# imu.net
KiCad netlist of a schematic drawn in EAGLE
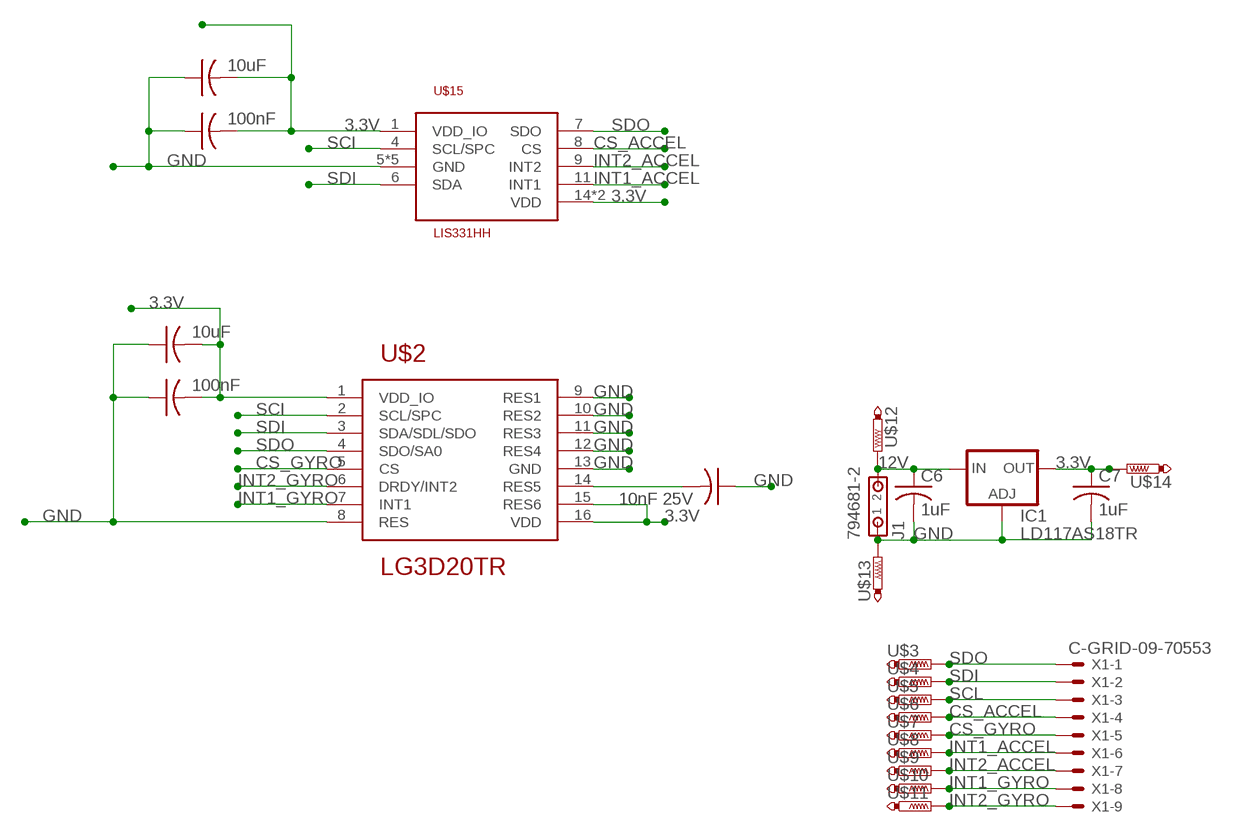
[diagram p0: schematic, sheet 1]

(export (version "E")
  (design (tool "Eeschema 10.0.6"))
  (components
    (comp (ref "C1_1")
      (value "10nF 25V")
      (footprint "eagle-import:C1206")
      (libsource (lib "eagle-import") (part "C-USC1206"))
    )
    (comp (ref "C2_1")
      (value "10uF")
      (footprint "eagle-import:C1206")
      (libsource (lib "eagle-import") (part "C-USC1206"))
    )
    (comp (ref "C3_1")
      (value "100nF")
      (footprint "eagle-import:C1206")
      (libsource (lib "eagle-import") (part "C-USC1206"))
    )
    (comp (ref "C4_1")
      (value "10uF")
      (footprint "eagle-import:C1206")
      (libsource (lib "eagle-import") (part "C-USC1206"))
    )
    (comp (ref "C5_1")
      (value "100nF")
      (footprint "eagle-import:C1206")
      (libsource (lib "eagle-import") (part "C-USC1206"))
    )
    (comp (ref "C6")
      (value "1uF")
      (footprint "eagle-import:C1206")
      (libsource (lib "eagle-import") (part "C-USC1206"))
    )
    (comp (ref "C7")
      (value "1uF")
      (footprint "eagle-import:C1206")
      (libsource (lib "eagle-import") (part "C-USC1206"))
    )
    (comp (ref "IC1")
      (value "LD117AS18TR")
      (footprint "eagle-import:SOT223")
      (libsource (lib "eagle-import") (part "LD117A?S18TR"))
    )
    (comp (ref "J1")
      (value "794681-2")
      (footprint "eagle-import:794681-2")
      (libsource (lib "eagle-import") (part "794681-2"))
    )
    (comp (ref "U$2")
      (value "LG3D20TR")
      (footprint "eagle-import:L3GD20TR")
      (libsource (lib "eagle-import") (part "LG3D20TR"))
    )
    (comp (ref "U$3")
      (value "TESTPAD-20MIL")
      (footprint "eagle-import:20MIL")
      (libsource (lib "eagle-import") (part "TESTPAD-20MIL"))
    )
    (comp (ref "U$4")
      (value "TESTPAD-20MIL")
      (footprint "eagle-import:20MIL")
      (libsource (lib "eagle-import") (part "TESTPAD-20MIL"))
    )
    (comp (ref "U$5")
      (value "TESTPAD-20MIL")
      (footprint "eagle-import:20MIL")
      (libsource (lib "eagle-import") (part "TESTPAD-20MIL"))
    )
    (comp (ref "U$6")
      (value "TESTPAD-20MIL")
      (footprint "eagle-import:20MIL")
      (libsource (lib "eagle-import") (part "TESTPAD-20MIL"))
    )
    (comp (ref "U$7")
      (value "TESTPAD-20MIL")
      (footprint "eagle-import:20MIL")
      (libsource (lib "eagle-import") (part "TESTPAD-20MIL"))
    )
    (comp (ref "U$8")
      (value "TESTPAD-20MIL")
      (footprint "eagle-import:20MIL")
      (libsource (lib "eagle-import") (part "TESTPAD-20MIL"))
    )
    (comp (ref "U$9")
      (value "TESTPAD-20MIL")
      (footprint "eagle-import:20MIL")
      (libsource (lib "eagle-import") (part "TESTPAD-20MIL"))
    )
    (comp (ref "U$10")
      (value "TESTPAD-20MIL")
      (footprint "eagle-import:20MIL")
      (libsource (lib "eagle-import") (part "TESTPAD-20MIL"))
    )
    (comp (ref "U$11")
      (value "TESTPAD-20MIL")
      (footprint "eagle-import:20MIL")
      (libsource (lib "eagle-import") (part "TESTPAD-20MIL"))
    )
    (comp (ref "U$12")
      (value "TESTPAD-20MIL")
      (footprint "eagle-import:20MIL")
      (libsource (lib "eagle-import") (part "TESTPAD-20MIL"))
    )
    (comp (ref "U$13")
      (value "TESTPAD-20MIL")
      (footprint "eagle-import:20MIL")
      (libsource (lib "eagle-import") (part "TESTPAD-20MIL"))
    )
    (comp (ref "U$14")
      (value "TESTPAD-20MIL")
      (footprint "eagle-import:20MIL")
      (libsource (lib "eagle-import") (part "TESTPAD-20MIL"))
    )
    (comp (ref "U$15")
      (value "LIS331HH")
      (footprint "eagle-import:LIS331HH")
      (libsource (lib "eagle-import") (part "LIS331HH"))
    )
    (comp (ref "X1")
      (value "C-GRID-09-70553")
      (footprint "eagle-import:70553-09")
      (libsource (lib "eagle-import") (part "C-GRID-09-70553"))
    )
  )
  (nets
    (net (code "1") (name "/3.3V") (class "Default")
      (node (ref "C2_1") (pin "2") (pinfunction "2_2") (pintype "passive"))
      (node (ref "C3_1") (pin "2") (pinfunction "2_2") (pintype "passive"))
      (node (ref "C4_1") (pin "2") (pinfunction "2_2") (pintype "passive"))
      (node (ref "C5_1") (pin "2") (pinfunction "2_2") (pintype "passive"))
      (node (ref "C7") (pin "1") (pinfunction "1_1") (pintype "passive"))
      (node (ref "IC1") (pin "4") (pinfunction "OUT_4") (pintype "passive"))
      (node (ref "U$14") (pin "P$1") (pinfunction "TP_P$1") (pintype "input"))
      (node (ref "U$15") (pin "1") (pinfunction "VDD_IO_1") (pintype "bidirectional"))
      (node (ref "U$15") (pin "14") (pinfunction "VDD_14") (pintype "bidirectional"))
      (node (ref "U$15") (pin "15") (pinfunction "VDD_15") (pintype "bidirectional"))
      (node (ref "U$2") (pin "1") (pinfunction "VDD_IO_1") (pintype "bidirectional"))
      (node (ref "U$2") (pin "15") (pinfunction "RES6_15") (pintype "bidirectional"))
      (node (ref "U$2") (pin "16") (pinfunction "VDD_16") (pintype "bidirectional"))
    )
    (net (code "2") (name "/12V") (class "Default")
      (node (ref "C6") (pin "1") (pinfunction "1_1") (pintype "passive"))
      (node (ref "IC1") (pin "3") (pinfunction "IN_3") (pintype "input"))
      (node (ref "J1") (pin "2") (pinfunction "2_2") (pintype "passive"))
      (node (ref "U$12") (pin "P$1") (pinfunction "TP_P$1") (pintype "input"))
    )
    (net (code "3") (name "/CS_ACCEL") (class "Default")
      (node (ref "U$15") (pin "8") (pinfunction "CS_8") (pintype "bidirectional"))
      (node (ref "U$6") (pin "P$1") (pinfunction "TP_P$1") (pintype "input"))
      (node (ref "X1") (pin "4") (pinfunction "S_4") (pintype "passive"))
    )
    (net (code "4") (name "/CS_GYRO") (class "Default")
      (node (ref "U$2") (pin "5") (pinfunction "CS_5") (pintype "bidirectional"))
      (node (ref "U$7") (pin "P$1") (pinfunction "TP_P$1") (pintype "input"))
      (node (ref "X1") (pin "5") (pinfunction "S_5") (pintype "passive"))
    )
    (net (code "5") (name "/GND") (class "Default")
      (node (ref "C1_1") (pin "1") (pinfunction "1_1") (pintype "passive"))
      (node (ref "C2_1") (pin "1") (pinfunction "1_1") (pintype "passive"))
      (node (ref "C3_1") (pin "1") (pinfunction "1_1") (pintype "passive"))
      (node (ref "C4_1") (pin "1") (pinfunction "1_1") (pintype "passive"))
      (node (ref "C5_1") (pin "1") (pinfunction "1_1") (pintype "passive"))
      (node (ref "C6") (pin "2") (pinfunction "2_2") (pintype "passive"))
      (node (ref "C7") (pin "2") (pinfunction "2_2") (pintype "passive"))
      (node (ref "IC1") (pin "1") (pinfunction "ADJ_1") (pintype "input"))
      (node (ref "J1") (pin "1") (pinfunction "1_1") (pintype "passive"))
      (node (ref "U$13") (pin "P$1") (pinfunction "TP_P$1") (pintype "input"))
      (node (ref "U$15") (pin "10") (pinfunction "GND_10") (pintype "bidirectional"))
      (node (ref "U$15") (pin "12") (pinfunction "GND_12") (pintype "bidirectional"))
      (node (ref "U$15") (pin "13") (pinfunction "GND_13") (pintype "bidirectional"))
      (node (ref "U$15") (pin "16") (pinfunction "GND_16") (pintype "bidirectional"))
      (node (ref "U$15") (pin "5") (pinfunction "GND_5") (pintype "bidirectional"))
      (node (ref "U$2") (pin "10") (pinfunction "RES2_10") (pintype "bidirectional"))
      (node (ref "U$2") (pin "11") (pinfunction "RES3_11") (pintype "bidirectional"))
      (node (ref "U$2") (pin "12") (pinfunction "RES4_12") (pintype "bidirectional"))
      (node (ref "U$2") (pin "13") (pinfunction "GND_13") (pintype "bidirectional"))
      (node (ref "U$2") (pin "8") (pinfunction "RES_8") (pintype "bidirectional"))
      (node (ref "U$2") (pin "9") (pinfunction "RES1_9") (pintype "bidirectional"))
    )
    (net (code "6") (name "/INT1_ACCEL") (class "Default")
      (node (ref "U$15") (pin "11") (pinfunction "INT1_11") (pintype "bidirectional"))
      (node (ref "U$8") (pin "P$1") (pinfunction "TP_P$1") (pintype "input"))
      (node (ref "X1") (pin "6") (pinfunction "S_6") (pintype "passive"))
    )
    (net (code "7") (name "/INT1_GYRO") (class "Default")
      (node (ref "U$10") (pin "P$1") (pinfunction "TP_P$1") (pintype "input"))
      (node (ref "U$2") (pin "7") (pinfunction "INT1_7") (pintype "bidirectional"))
      (node (ref "X1") (pin "8") (pinfunction "S_8") (pintype "passive"))
    )
    (net (code "8") (name "/INT2_ACCEL") (class "Default")
      (node (ref "U$15") (pin "9") (pinfunction "INT2_9") (pintype "bidirectional"))
      (node (ref "U$9") (pin "P$1") (pinfunction "TP_P$1") (pintype "input"))
      (node (ref "X1") (pin "7") (pinfunction "S_7") (pintype "passive"))
    )
    (net (code "9") (name "/INT2_GYRO") (class "Default")
      (node (ref "U$11") (pin "P$1") (pinfunction "TP_P$1") (pintype "input"))
      (node (ref "U$2") (pin "6") (pinfunction "DRDY/INT2_6") (pintype "bidirectional"))
      (node (ref "X1") (pin "9") (pinfunction "S_9") (pintype "passive"))
    )
    (net (code "10") (name "/SCI") (class "Default")
      (node (ref "U$15") (pin "4") (pinfunction "SCL/SPC_4") (pintype "bidirectional"))
      (node (ref "U$2") (pin "2") (pinfunction "SCL/SPC_2") (pintype "bidirectional"))
    )
    (net (code "11") (name "/SCL") (class "Default")
      (node (ref "U$5") (pin "P$1") (pinfunction "TP_P$1") (pintype "input"))
      (node (ref "X1") (pin "3") (pinfunction "S_3") (pintype "passive"))
    )
    (net (code "12") (name "/SDI") (class "Default")
      (node (ref "U$15") (pin "6") (pinfunction "SDA_6") (pintype "bidirectional"))
      (node (ref "U$2") (pin "3") (pinfunction "SDA/SDL/SDO_3") (pintype "bidirectional"))
      (node (ref "U$4") (pin "P$1") (pinfunction "TP_P$1") (pintype "input"))
      (node (ref "X1") (pin "2") (pinfunction "S_2") (pintype "passive"))
    )
    (net (code "13") (name "/SDO") (class "Default")
      (node (ref "U$15") (pin "7") (pinfunction "SDO_7") (pintype "bidirectional"))
      (node (ref "U$2") (pin "4") (pinfunction "SDO/SA0_4") (pintype "bidirectional"))
      (node (ref "U$3") (pin "P$1") (pinfunction "TP_P$1") (pintype "input"))
      (node (ref "X1") (pin "1") (pinfunction "S_1") (pintype "passive"))
    )
    (net (code "14") (name "Net-(U$2-RES5)") (class "Default")
      (node (ref "C1_1") (pin "2") (pinfunction "2_2") (pintype "passive"))
      (node (ref "U$2") (pin "14") (pinfunction "RES5_14") (pintype "bidirectional"))
    )
  )
)
